# I2C_UV_Sensor.net
KiCad netlist of a schematic drawn in Altium Designer
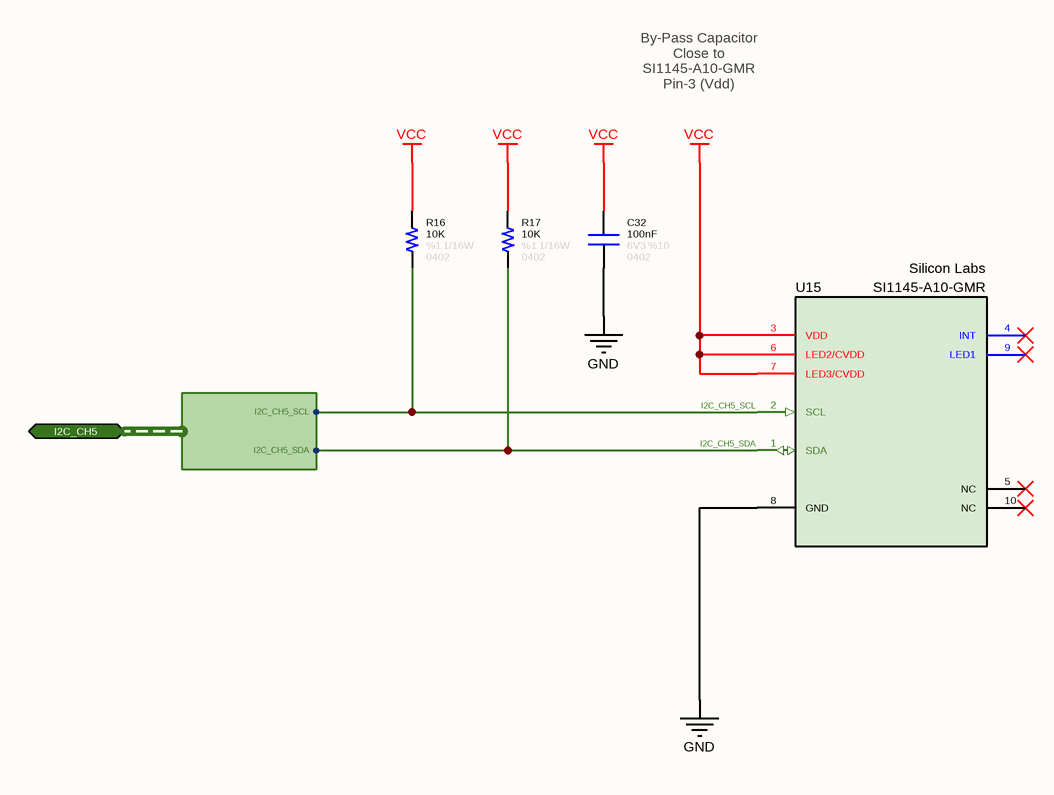
[diagram p0: I2C UV Sensor.SchDoc]

(export (version "E")
  (design (tool "Eeschema 10.0.6"))
  (components
    (comp (ref "C32")
      (value "100nF")
      (footprint "CAPACITOR_0402")
      (description "Capacitor - 100nF [0402-6V3] (Ceramic)")
      (fields
        (field (name "MANUFACTURER PART NUMBER") "04026D104KAT4A")
        (field (name "TOLERANCE") "%10")
        (field (name "VOLTAGE") "6V3")
        (field (name "CASE") "0402")
        (field (name "Comment") "Capacitor - 100nF [0402] (Ceramic)")
      )
      (libsource (lib "P101DA_Library") (part "Capacitor - 100nF [0402-6V3]"))
    )
    (comp (ref "R16")
      (value "10K")
      (footprint "RESISTOR_0402")
      (description "Thick Film Resistors - SMD 1/16 W 10 KOhm 1%")
      (fields
        (field (name "MANUFACTURER PART NUMBER") "CRCW040210K0FKED")
        (field (name "TOLERANCE") "%1")
        (field (name "CASE") "0402")
        (field (name "POWER") "1/16W")
        (field (name "Comment") "10K - 0402 - %1 - 1/16W")
      )
      (libsource (lib "P101DA_Library") (part "Resistor - 10K [0402]"))
    )
    (comp (ref "R17")
      (value "10K")
      (footprint "RESISTOR_0402")
      (description "Thick Film Resistors - SMD 1/16 W 10 KOhm 1%")
      (fields
        (field (name "MANUFACTURER PART NUMBER") "CRCW040210K0FKED")
        (field (name "TOLERANCE") "%1")
        (field (name "CASE") "0402")
        (field (name "POWER") "1/16W")
        (field (name "Comment") "10K - 0402 - %1 - 1/16W")
      )
      (libsource (lib "P101DA_Library") (part "Resistor - 10K [0402]"))
    )
    (comp (ref "U15")
      (value "Si1145-A10-GMR")
      (footprint "SI1145")
      (description "Proximity Sensors I2C UV Index and Proximity/Ambient Light Sensor with 1 LED Driver")
      (fields
        (field (name "MANUFACTURER PART NUMBER") "SI1145-A10-GMR")
        (field (name "MANUFACTURER NAME") "Silicon Labs")
      )
      (libsource (lib "P101DA_Library") (part "IC - Si1145-A10-GMR"))
    )
  )
  (nets
    (net (code "2") (name "/I2C_CH5_SCL") (class "Default")
      (node (ref "R16") (pin "1") (pinfunction "1_1") (pintype "passive"))
      (node (ref "U15") (pin "2") (pinfunction "SCL_2") (pintype "input"))
    )
    (net (code "3") (name "/I2C_CH5_SDA") (class "Default")
      (node (ref "R17") (pin "1") (pinfunction "1_1") (pintype "passive"))
      (node (ref "U15") (pin "1") (pinfunction "SDA_1") (pintype "bidirectional"))
    )
    (net (code "5") (name "GND") (class "Default")
      (node (ref "C32") (pin "1") (pinfunction "1_1") (pintype "passive"))
      (node (ref "U15") (pin "8") (pinfunction "GND_8") (pintype "power_in"))
    )
    (net (code "6") (name "VCC") (class "Default")
      (node (ref "C32") (pin "2") (pinfunction "2_2") (pintype "passive"))
      (node (ref "R16") (pin "2") (pinfunction "2_2") (pintype "passive"))
      (node (ref "R17") (pin "2") (pinfunction "2_2") (pintype "passive"))
      (node (ref "U15") (pin "3") (pinfunction "VDD_3") (pintype "power_in"))
      (node (ref "U15") (pin "6") (pinfunction "LED2/CVDD_6") (pintype "power_in"))
      (node (ref "U15") (pin "7") (pinfunction "LED3/CVDD_7") (pintype "power_in"))
    )
    (net (code "7") (name "unconnected-(U15-INT-Pad4)") (class "Default")
      (node (ref "U15") (pin "4") (pinfunction "INT_4") (pintype "passive+no_connect"))
    )
    (net (code "8") (name "unconnected-(U15-LED1-Pad9)") (class "Default")
      (node (ref "U15") (pin "9") (pinfunction "LED1_9") (pintype "passive+no_connect"))
    )
    (net (code "9") (name "unconnected-(U15-NC-Pad5)") (class "Default")
      (node (ref "U15") (pin "5") (pinfunction "NC_5") (pintype "passive+no_connect"))
    )
    (net (code "10") (name "unconnected-(U15-NC-Pad10)") (class "Default")
      (node (ref "U15") (pin "10") (pinfunction "NC_10") (pintype "passive+no_connect"))
    )
  )
)
